# 3400.net
KiCad netlist of a schematic drawn in EAGLE
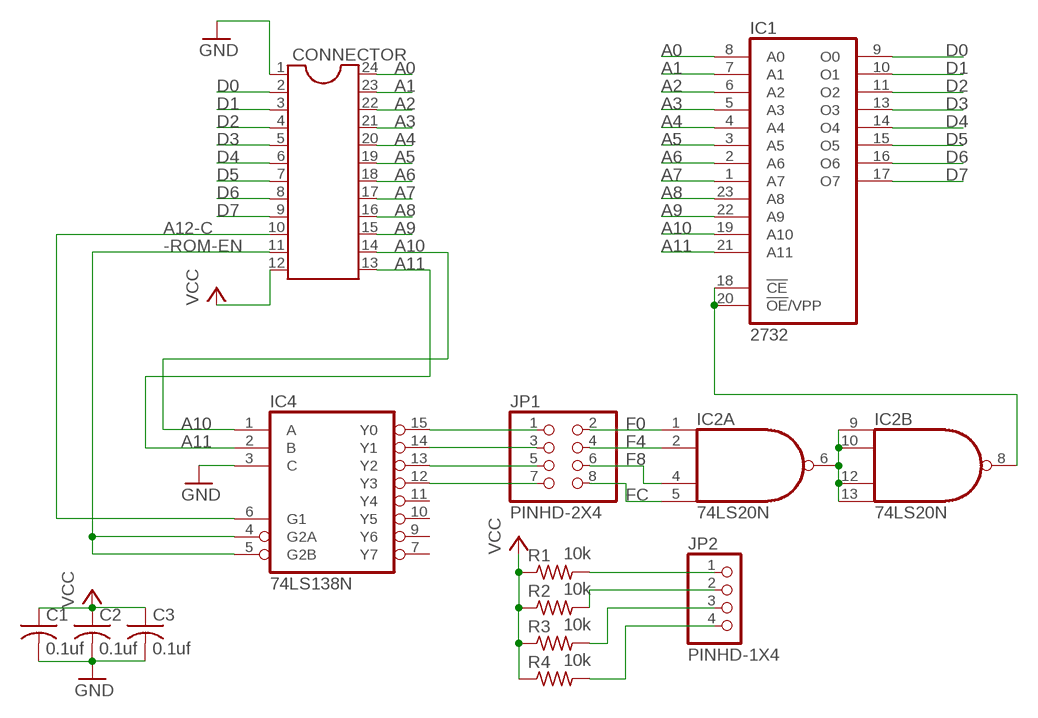
[diagram p0: schematic, sheet 1]

(export (version "E")
  (design (tool "Eeschema 10.0.6"))
  (components
    (comp (ref "C1")
      (value "0.1uf")
      (footprint "eagle-import:C025-024X044")
      (libsource (lib "eagle-import") (part "C-US025-024X044"))
    )
    (comp (ref "C2")
      (value "0.1uf")
      (footprint "eagle-import:C025-024X044")
      (libsource (lib "eagle-import") (part "C-US025-024X044"))
    )
    (comp (ref "C3")
      (value "0.1uf")
      (footprint "eagle-import:C025-024X044")
      (libsource (lib "eagle-import") (part "C-US025-024X044"))
    )
    (comp (ref "CONNECTOR")
      (value "DIL24-6")
      (footprint "eagle-import:DIL24-6")
      (libsource (lib "eagle-import") (part "DIL24-6"))
    )
    (comp (ref "IC1")
      (value "2732")
      (footprint "eagle-import:DIL24")
      (libsource (lib "eagle-import") (part "2732"))
    )
    (comp (ref "IC2")
      (value "74LS20N")
      (footprint "eagle-import:DIL14")
      (libsource (lib "eagle-import") (part "7420NLS"))
    )
    (comp (ref "IC4")
      (value "74LS138N")
      (footprint "eagle-import:DIL16")
      (libsource (lib "eagle-import") (part "74138NLS"))
    )
    (comp (ref "JP1")
      (value "PINHD-2X4")
      (footprint "eagle-import:2X04")
      (libsource (lib "eagle-import") (part "PINHD-2X4"))
    )
    (comp (ref "JP2")
      (value "PINHD-1X4")
      (footprint "eagle-import:1X04")
      (libsource (lib "eagle-import") (part "PINHD-1X4"))
    )
    (comp (ref "R1")
      (value "10k")
      (footprint "eagle-import:0207_10")
      (libsource (lib "eagle-import") (part "R-US_0207/10"))
    )
    (comp (ref "R2")
      (value "10k")
      (footprint "eagle-import:0207_10")
      (libsource (lib "eagle-import") (part "R-US_0207/10"))
    )
    (comp (ref "R3")
      (value "10k")
      (footprint "eagle-import:0207_10")
      (libsource (lib "eagle-import") (part "R-US_0207/10"))
    )
    (comp (ref "R4")
      (value "10k")
      (footprint "eagle-import:0207_10")
      (libsource (lib "eagle-import") (part "R-US_0207/10"))
    )
  )
  (nets
    (net (code "1") (name "/-ROM-EN") (class "Default")
      (node (ref "CONNECTOR") (pin "11") (pinfunction "11_11") (pintype "passive"))
      (node (ref "IC4") (pin "4") (pinfunction "G2A_4") (pintype "input"))
      (node (ref "IC4") (pin "5") (pinfunction "G2B_5") (pintype "input"))
    )
    (net (code "2") (name "/A0") (class "Default")
      (node (ref "CONNECTOR") (pin "24") (pinfunction "24_24") (pintype "passive"))
      (node (ref "IC1") (pin "8") (pinfunction "A0_8") (pintype "input"))
    )
    (net (code "3") (name "/A1") (class "Default")
      (node (ref "CONNECTOR") (pin "23") (pinfunction "23_23") (pintype "passive"))
      (node (ref "IC1") (pin "7") (pinfunction "A1_7") (pintype "input"))
    )
    (net (code "4") (name "/A2") (class "Default")
      (node (ref "CONNECTOR") (pin "22") (pinfunction "22_22") (pintype "passive"))
      (node (ref "IC1") (pin "6") (pinfunction "A2_6") (pintype "input"))
    )
    (net (code "5") (name "/A3") (class "Default")
      (node (ref "CONNECTOR") (pin "21") (pinfunction "21_21") (pintype "passive"))
      (node (ref "IC1") (pin "5") (pinfunction "A3_5") (pintype "input"))
    )
    (net (code "6") (name "/A4") (class "Default")
      (node (ref "CONNECTOR") (pin "20") (pinfunction "20_20") (pintype "passive"))
      (node (ref "IC1") (pin "4") (pinfunction "A4_4") (pintype "input"))
    )
    (net (code "7") (name "/A5") (class "Default")
      (node (ref "CONNECTOR") (pin "19") (pinfunction "19_19") (pintype "passive"))
      (node (ref "IC1") (pin "3") (pinfunction "A5_3") (pintype "input"))
    )
    (net (code "8") (name "/A6") (class "Default")
      (node (ref "CONNECTOR") (pin "18") (pinfunction "18_18") (pintype "passive"))
      (node (ref "IC1") (pin "2") (pinfunction "A6_2") (pintype "input"))
    )
    (net (code "9") (name "/A7") (class "Default")
      (node (ref "CONNECTOR") (pin "17") (pinfunction "17_17") (pintype "passive"))
      (node (ref "IC1") (pin "1") (pinfunction "A7_1") (pintype "input"))
    )
    (net (code "10") (name "/A8") (class "Default")
      (node (ref "CONNECTOR") (pin "16") (pinfunction "16_16") (pintype "passive"))
      (node (ref "IC1") (pin "23") (pinfunction "A8_23") (pintype "input"))
    )
    (net (code "11") (name "/A9") (class "Default")
      (node (ref "CONNECTOR") (pin "15") (pinfunction "15_15") (pintype "passive"))
      (node (ref "IC1") (pin "22") (pinfunction "A9_22") (pintype "input"))
    )
    (net (code "12") (name "/A10") (class "Default")
      (node (ref "CONNECTOR") (pin "14") (pinfunction "14_14") (pintype "passive"))
      (node (ref "IC1") (pin "19") (pinfunction "A10_19") (pintype "input"))
      (node (ref "IC4") (pin "1") (pinfunction "A_1") (pintype "input"))
    )
    (net (code "13") (name "/A11") (class "Default")
      (node (ref "CONNECTOR") (pin "13") (pinfunction "13_13") (pintype "passive"))
      (node (ref "IC1") (pin "21") (pinfunction "A11_21") (pintype "input"))
      (node (ref "IC4") (pin "2") (pinfunction "B_2") (pintype "input"))
    )
    (net (code "14") (name "/A12-C") (class "Default")
      (node (ref "CONNECTOR") (pin "10") (pinfunction "10_10") (pintype "passive"))
      (node (ref "IC4") (pin "6") (pinfunction "G1_6") (pintype "input"))
    )
    (net (code "15") (name "/D0") (class "Default")
      (node (ref "CONNECTOR") (pin "2") (pinfunction "2_2") (pintype "passive"))
      (node (ref "IC1") (pin "9") (pinfunction "O0_9") (pintype "tri_state"))
    )
    (net (code "16") (name "/D1") (class "Default")
      (node (ref "CONNECTOR") (pin "3") (pinfunction "3_3") (pintype "passive"))
      (node (ref "IC1") (pin "10") (pinfunction "O1_10") (pintype "tri_state"))
    )
    (net (code "17") (name "/D2") (class "Default")
      (node (ref "CONNECTOR") (pin "4") (pinfunction "4_4") (pintype "passive"))
      (node (ref "IC1") (pin "11") (pinfunction "O2_11") (pintype "tri_state"))
    )
    (net (code "18") (name "/D3") (class "Default")
      (node (ref "CONNECTOR") (pin "5") (pinfunction "5_5") (pintype "passive"))
      (node (ref "IC1") (pin "13") (pinfunction "O3_13") (pintype "tri_state"))
    )
    (net (code "19") (name "/D4") (class "Default")
      (node (ref "CONNECTOR") (pin "6") (pinfunction "6_6") (pintype "passive"))
      (node (ref "IC1") (pin "14") (pinfunction "O4_14") (pintype "tri_state"))
    )
    (net (code "20") (name "/D5") (class "Default")
      (node (ref "CONNECTOR") (pin "7") (pinfunction "7_7") (pintype "passive"))
      (node (ref "IC1") (pin "15") (pinfunction "O5_15") (pintype "tri_state"))
    )
    (net (code "21") (name "/D6") (class "Default")
      (node (ref "CONNECTOR") (pin "8") (pinfunction "8_8") (pintype "passive"))
      (node (ref "IC1") (pin "16") (pinfunction "O6_16") (pintype "tri_state"))
    )
    (net (code "22") (name "/D7") (class "Default")
      (node (ref "CONNECTOR") (pin "9") (pinfunction "9_9") (pintype "passive"))
      (node (ref "IC1") (pin "17") (pinfunction "O7_17") (pintype "tri_state"))
    )
    (net (code "23") (name "/F0") (class "Default")
      (node (ref "IC2") (pin "1") (pinfunction "I0_1") (pintype "input"))
      (node (ref "JP1") (pin "2") (pinfunction "2_2") (pintype "passive"))
    )
    (net (code "24") (name "/F4") (class "Default")
      (node (ref "IC2") (pin "2") (pinfunction "I1_2") (pintype "input"))
      (node (ref "JP1") (pin "4") (pinfunction "4_4") (pintype "passive"))
    )
    (net (code "25") (name "/F8") (class "Default")
      (node (ref "IC2") (pin "4") (pinfunction "I2_4") (pintype "input"))
      (node (ref "JP1") (pin "6") (pinfunction "6_6") (pintype "passive"))
    )
    (net (code "26") (name "/FC") (class "Default")
      (node (ref "IC2") (pin "5") (pinfunction "I3_5") (pintype "input"))
      (node (ref "JP1") (pin "8") (pinfunction "8_8") (pintype "passive"))
    )
    (net (code "27") (name "GND") (class "Default")
      (node (ref "C1") (pin "2") (pinfunction "2_2") (pintype "passive"))
      (node (ref "C2") (pin "2") (pinfunction "2_2") (pintype "passive"))
      (node (ref "C3") (pin "2") (pinfunction "2_2") (pintype "passive"))
      (node (ref "CONNECTOR") (pin "1") (pinfunction "1_1") (pintype "passive"))
      (node (ref "IC4") (pin "3") (pinfunction "C_3") (pintype "input"))
    )
    (net (code "28") (name "Net-(IC1A-~{CE})") (class "Default")
      (node (ref "IC1") (pin "18") (pinfunction "~{CE}_18") (pintype "input"))
      (node (ref "IC1") (pin "20") (pinfunction "~{OE}/VPP_20") (pintype "input"))
      (node (ref "IC2") (pin "8") (pinfunction "O_8") (pintype "output"))
    )
    (net (code "29") (name "Net-(IC2A-O)") (class "Default")
      (node (ref "IC2") (pin "10") (pinfunction "I1_10") (pintype "input"))
      (node (ref "IC2") (pin "12") (pinfunction "I2_12") (pintype "input"))
      (node (ref "IC2") (pin "13") (pinfunction "I3_13") (pintype "input"))
      (node (ref "IC2") (pin "6") (pinfunction "O_6") (pintype "output"))
      (node (ref "IC2") (pin "9") (pinfunction "I0_9") (pintype "input"))
    )
    (net (code "30") (name "Net-(IC4A-Y0)") (class "Default")
      (node (ref "IC4") (pin "15") (pinfunction "Y0_15") (pintype "output"))
      (node (ref "JP1") (pin "1") (pinfunction "1_1") (pintype "passive"))
    )
    (net (code "31") (name "Net-(IC4A-Y1)") (class "Default")
      (node (ref "IC4") (pin "14") (pinfunction "Y1_14") (pintype "output"))
      (node (ref "JP1") (pin "3") (pinfunction "3_3") (pintype "passive"))
    )
    (net (code "32") (name "Net-(IC4A-Y2)") (class "Default")
      (node (ref "IC4") (pin "13") (pinfunction "Y2_13") (pintype "output"))
      (node (ref "JP1") (pin "5") (pinfunction "5_5") (pintype "passive"))
    )
    (net (code "33") (name "Net-(IC4A-Y3)") (class "Default")
      (node (ref "IC4") (pin "12") (pinfunction "Y3_12") (pintype "output"))
      (node (ref "JP1") (pin "7") (pinfunction "7_7") (pintype "passive"))
    )
    (net (code "34") (name "Net-(JP2-Pad1)") (class "Default")
      (node (ref "JP2") (pin "1") (pinfunction "1_1") (pintype "passive"))
      (node (ref "R1") (pin "2") (pinfunction "2_2") (pintype "passive"))
    )
    (net (code "35") (name "Net-(JP2-Pad2)") (class "Default")
      (node (ref "JP2") (pin "2") (pinfunction "2_2") (pintype "passive"))
      (node (ref "R2") (pin "2") (pinfunction "2_2") (pintype "passive"))
    )
    (net (code "36") (name "Net-(JP2-Pad3)") (class "Default")
      (node (ref "JP2") (pin "3") (pinfunction "3_3") (pintype "passive"))
      (node (ref "R3") (pin "2") (pinfunction "2_2") (pintype "passive"))
    )
    (net (code "37") (name "Net-(JP2-Pad4)") (class "Default")
      (node (ref "JP2") (pin "4") (pinfunction "4_4") (pintype "passive"))
      (node (ref "R4") (pin "2") (pinfunction "2_2") (pintype "passive"))
    )
    (net (code "38") (name "VCC") (class "Default")
      (node (ref "C1") (pin "1") (pinfunction "1_1") (pintype "passive"))
      (node (ref "C2") (pin "1") (pinfunction "1_1") (pintype "passive"))
      (node (ref "C3") (pin "1") (pinfunction "1_1") (pintype "passive"))
      (node (ref "CONNECTOR") (pin "12") (pinfunction "12_12") (pintype "passive"))
      (node (ref "R1") (pin "1") (pinfunction "1_1") (pintype "passive"))
      (node (ref "R2") (pin "1") (pinfunction "1_1") (pintype "passive"))
      (node (ref "R3") (pin "1") (pinfunction "1_1") (pintype "passive"))
      (node (ref "R4") (pin "1") (pinfunction "1_1") (pintype "passive"))
    )
    (net (code "39") (name "unconnected-(IC4A-Y4-Pad11)") (class "Default")
      (node (ref "IC4") (pin "11") (pinfunction "Y4_11") (pintype "output"))
    )
    (net (code "40") (name "unconnected-(IC4A-Y5-Pad10)") (class "Default")
      (node (ref "IC4") (pin "10") (pinfunction "Y5_10") (pintype "output"))
    )
    (net (code "41") (name "unconnected-(IC4A-Y6-Pad9)") (class "Default")
      (node (ref "IC4") (pin "9") (pinfunction "Y6_9") (pintype "output"))
    )
    (net (code "42") (name "unconnected-(IC4A-Y7-Pad7)") (class "Default")
      (node (ref "IC4") (pin "7") (pinfunction "Y7_7") (pintype "output"))
    )
  )
)
